# lightsaber.net
KiCad netlist of a schematic drawn in EAGLE
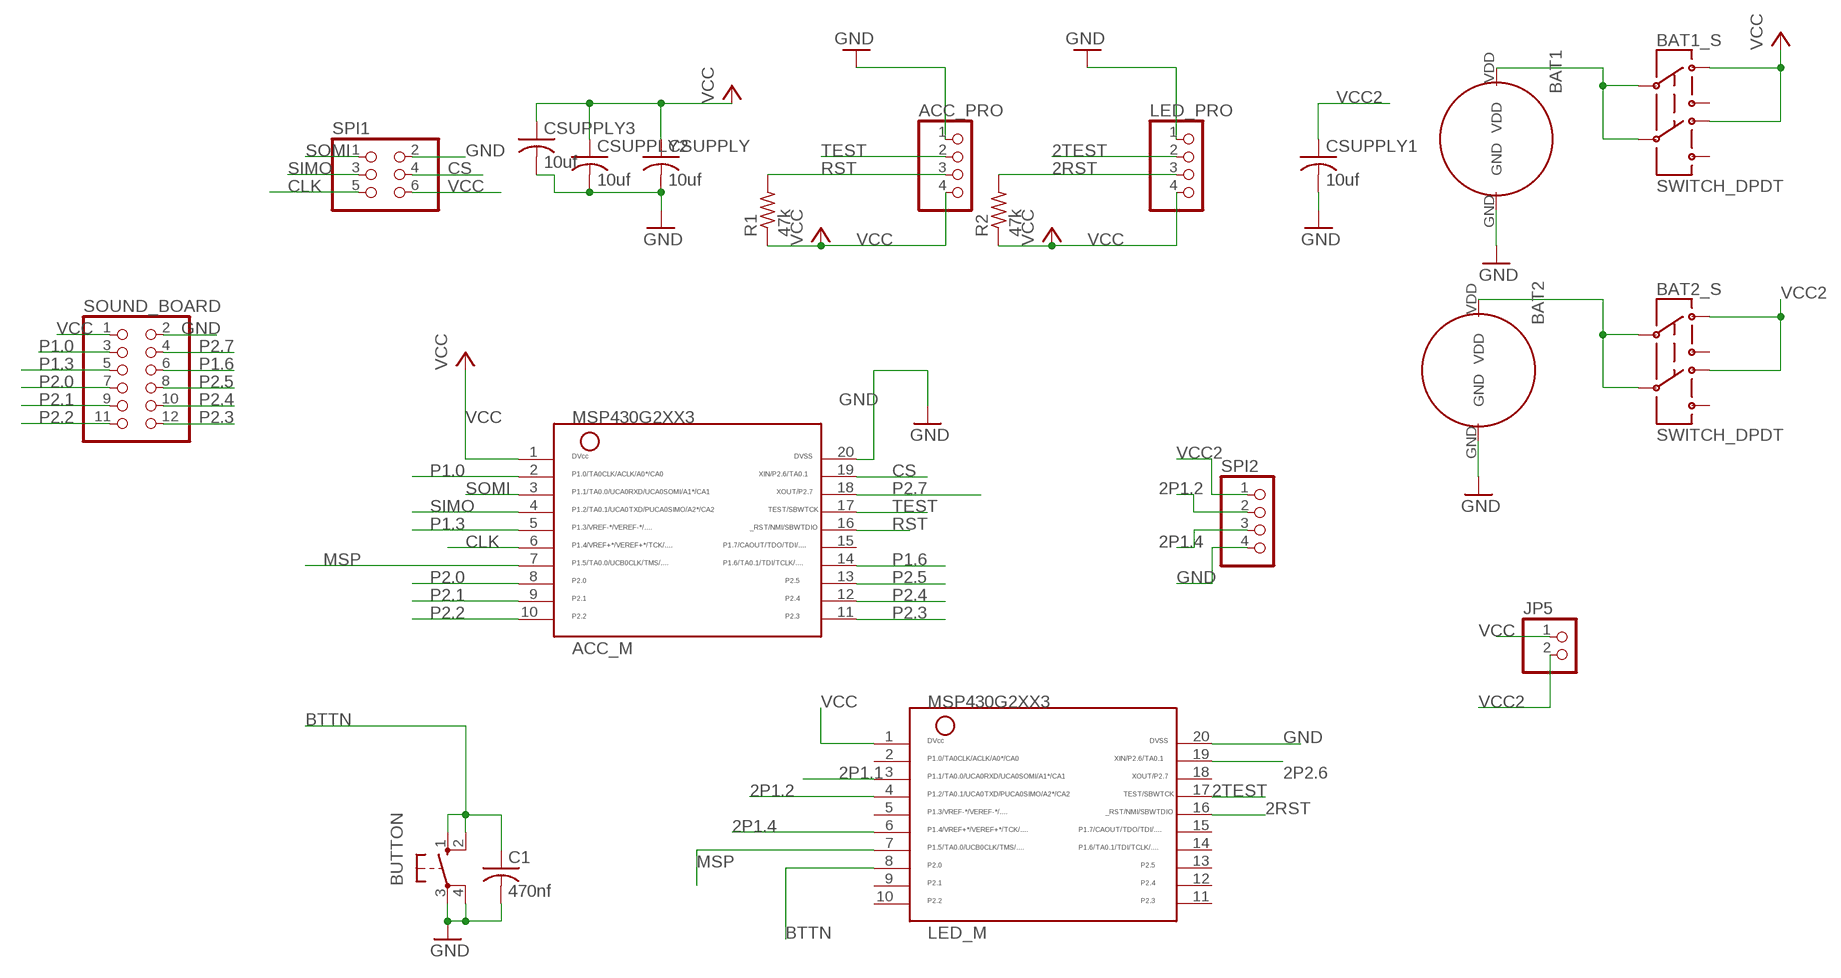
[diagram p0: schematic, sheet 1]

(export (version "E")
  (design (tool "Eeschema 10.0.6"))
  (components
    (comp (ref "ACC_M")
      (value "MSP430G2XX3TSSOP")
      (footprint "eagle-import:PW20")
      (libsource (lib "eagle-import") (part "MSP430G2XX3TSSOP"))
    )
    (comp (ref "ACC_PRO")
      (value "PINHD-1X4")
      (footprint "eagle-import:1X04")
      (libsource (lib "eagle-import") (part "PINHD-1X4"))
    )
    (comp (ref "BAT1")
      (value "BAT_PAD")
      (footprint "eagle-import:BATTERY_PAD1")
      (libsource (lib "eagle-import") (part "BAT_PAD"))
    )
    (comp (ref "BAT1_S")
      (value "SWITCH_DPDT")
      (footprint "eagle-import:JS_DPDT_TH")
      (libsource (lib "eagle-import") (part "SWITCH_DPDT"))
    )
    (comp (ref "BAT2")
      (value "BAT_PAD")
      (footprint "eagle-import:BATTERY_PAD1")
      (libsource (lib "eagle-import") (part "BAT_PAD"))
    )
    (comp (ref "BAT2_S")
      (value "SWITCH_DPDT")
      (footprint "eagle-import:JS_DPDT_TH")
      (libsource (lib "eagle-import") (part "SWITCH_DPDT"))
    )
    (comp (ref "BUTTON")
      (value "10-XX")
      (footprint "eagle-import:B3F-10XX")
      (fields (field (name "MPN") "B3F-1000"))
      (libsource (lib "eagle-import") (part "10-XX"))
    )
    (comp (ref "C1")
      (value "470nf")
      (footprint "eagle-import:C1206")
      (libsource (lib "eagle-import") (part "C-USC1206"))
    )
    (comp (ref "CSUPPLY")
      (value "10uf")
      (footprint "eagle-import:C1206")
      (libsource (lib "eagle-import") (part "C-USC1206"))
    )
    (comp (ref "CSUPPLY1")
      (value "10uf")
      (footprint "eagle-import:C1206")
      (libsource (lib "eagle-import") (part "C-USC1206"))
    )
    (comp (ref "CSUPPLY2")
      (value "10uf")
      (footprint "eagle-import:C1206")
      (libsource (lib "eagle-import") (part "C-USC1206"))
    )
    (comp (ref "CSUPPLY3")
      (value "10uf")
      (footprint "eagle-import:C1206")
      (libsource (lib "eagle-import") (part "C-USC1206"))
    )
    (comp (ref "JP5")
      (value "PINHD-1X2")
      (footprint "eagle-import:1X02")
      (libsource (lib "eagle-import") (part "PINHD-1X2"))
    )
    (comp (ref "LED_M")
      (value "MSP430G2XX3TSSOP")
      (footprint "eagle-import:PW20")
      (libsource (lib "eagle-import") (part "MSP430G2XX3TSSOP"))
    )
    (comp (ref "LED_PRO")
      (value "PINHD-1X4")
      (footprint "eagle-import:1X04")
      (libsource (lib "eagle-import") (part "PINHD-1X4"))
    )
    (comp (ref "R1")
      (value "47k")
      (footprint "eagle-import:R1206")
      (libsource (lib "eagle-import") (part "R-US_R1206"))
    )
    (comp (ref "R2")
      (value "47k")
      (footprint "eagle-import:R1206")
      (libsource (lib "eagle-import") (part "R-US_R1206"))
    )
    (comp (ref "SOUND_BOARD")
      (value "PINHD-2X6")
      (footprint "eagle-import:2X06")
      (libsource (lib "eagle-import") (part "PINHD-2X6"))
    )
    (comp (ref "SPI1")
      (value "PINHD-2X3")
      (footprint "eagle-import:2X03")
      (libsource (lib "eagle-import") (part "PINHD-2X3"))
    )
    (comp (ref "SPI2")
      (value "PINHD-1X4")
      (footprint "eagle-import:1X04")
      (libsource (lib "eagle-import") (part "PINHD-1X4"))
    )
  )
  (nets
    (net (code "1") (name "/2P1.1") (class "Default")
      (node (ref "LED_M") (pin "3") (pinfunction "3_3") (pintype "bidirectional"))
    )
    (net (code "2") (name "/2P1.2") (class "Default")
      (node (ref "LED_M") (pin "4") (pinfunction "4_4") (pintype "bidirectional"))
      (node (ref "SPI2") (pin "2") (pinfunction "2_2") (pintype "passive"))
    )
    (net (code "3") (name "/2P1.4") (class "Default")
      (node (ref "LED_M") (pin "6") (pinfunction "6_6") (pintype "bidirectional"))
      (node (ref "SPI2") (pin "3") (pinfunction "3_3") (pintype "passive"))
    )
    (net (code "4") (name "/2P2.6") (class "Default")
      (node (ref "LED_M") (pin "19") (pinfunction "19_19") (pintype "bidirectional"))
    )
    (net (code "5") (name "/2RST") (class "Default")
      (node (ref "LED_M") (pin "16") (pinfunction "16_16") (pintype "bidirectional"))
      (node (ref "LED_PRO") (pin "3") (pinfunction "3_3") (pintype "passive"))
      (node (ref "R2") (pin "2") (pinfunction "2_2") (pintype "passive"))
    )
    (net (code "6") (name "/2TEST") (class "Default")
      (node (ref "LED_M") (pin "17") (pinfunction "17_17") (pintype "bidirectional"))
      (node (ref "LED_PRO") (pin "2") (pinfunction "2_2") (pintype "passive"))
    )
    (net (code "7") (name "/BTTN") (class "Default")
      (node (ref "BUTTON") (pin "1") (pinfunction "S_1") (pintype "passive"))
      (node (ref "BUTTON") (pin "2") (pinfunction "S1_2") (pintype "passive"))
      (node (ref "C1") (pin "1") (pinfunction "1_1") (pintype "passive"))
      (node (ref "LED_M") (pin "8") (pinfunction "8_8") (pintype "bidirectional"))
    )
    (net (code "8") (name "/CLK") (class "Default")
      (node (ref "ACC_M") (pin "6") (pinfunction "6_6") (pintype "bidirectional"))
      (node (ref "SPI1") (pin "5") (pinfunction "5_5") (pintype "passive"))
    )
    (net (code "9") (name "/CS") (class "Default")
      (node (ref "ACC_M") (pin "19") (pinfunction "19_19") (pintype "bidirectional"))
      (node (ref "SPI1") (pin "4") (pinfunction "4_4") (pintype "passive"))
    )
    (net (code "10") (name "/MSP") (class "Default")
      (node (ref "ACC_M") (pin "7") (pinfunction "7_7") (pintype "bidirectional"))
      (node (ref "LED_M") (pin "7") (pinfunction "7_7") (pintype "bidirectional"))
    )
    (net (code "11") (name "/P1.0") (class "Default")
      (node (ref "ACC_M") (pin "2") (pinfunction "2_2") (pintype "bidirectional"))
      (node (ref "SOUND_BOARD") (pin "3") (pinfunction "3_3") (pintype "passive"))
    )
    (net (code "12") (name "/P1.3") (class "Default")
      (node (ref "ACC_M") (pin "5") (pinfunction "5_5") (pintype "bidirectional"))
      (node (ref "SOUND_BOARD") (pin "5") (pinfunction "5_5") (pintype "passive"))
    )
    (net (code "13") (name "/P1.6") (class "Default")
      (node (ref "ACC_M") (pin "14") (pinfunction "14_14") (pintype "bidirectional"))
      (node (ref "SOUND_BOARD") (pin "6") (pinfunction "6_6") (pintype "passive"))
    )
    (net (code "14") (name "/P2.0") (class "Default")
      (node (ref "ACC_M") (pin "8") (pinfunction "8_8") (pintype "bidirectional"))
      (node (ref "SOUND_BOARD") (pin "7") (pinfunction "7_7") (pintype "passive"))
    )
    (net (code "15") (name "/P2.1") (class "Default")
      (node (ref "ACC_M") (pin "9") (pinfunction "9_9") (pintype "bidirectional"))
      (node (ref "SOUND_BOARD") (pin "9") (pinfunction "9_9") (pintype "passive"))
    )
    (net (code "16") (name "/P2.2") (class "Default")
      (node (ref "ACC_M") (pin "10") (pinfunction "10_10") (pintype "bidirectional"))
      (node (ref "SOUND_BOARD") (pin "11") (pinfunction "11_11") (pintype "passive"))
    )
    (net (code "17") (name "/P2.3") (class "Default")
      (node (ref "ACC_M") (pin "11") (pinfunction "11_11") (pintype "bidirectional"))
      (node (ref "SOUND_BOARD") (pin "12") (pinfunction "12_12") (pintype "passive"))
    )
    (net (code "18") (name "/P2.4") (class "Default")
      (node (ref "ACC_M") (pin "12") (pinfunction "12_12") (pintype "bidirectional"))
      (node (ref "SOUND_BOARD") (pin "10") (pinfunction "10_10") (pintype "passive"))
    )
    (net (code "19") (name "/P2.5") (class "Default")
      (node (ref "ACC_M") (pin "13") (pinfunction "13_13") (pintype "bidirectional"))
      (node (ref "SOUND_BOARD") (pin "8") (pinfunction "8_8") (pintype "passive"))
    )
    (net (code "20") (name "/P2.7") (class "Default")
      (node (ref "ACC_M") (pin "18") (pinfunction "18_18") (pintype "bidirectional"))
      (node (ref "SOUND_BOARD") (pin "4") (pinfunction "4_4") (pintype "passive"))
    )
    (net (code "21") (name "/RST") (class "Default")
      (node (ref "ACC_M") (pin "16") (pinfunction "16_16") (pintype "bidirectional"))
      (node (ref "ACC_PRO") (pin "3") (pinfunction "3_3") (pintype "passive"))
      (node (ref "R1") (pin "2") (pinfunction "2_2") (pintype "passive"))
    )
    (net (code "22") (name "/SIMO") (class "Default")
      (node (ref "ACC_M") (pin "4") (pinfunction "4_4") (pintype "bidirectional"))
      (node (ref "SPI1") (pin "3") (pinfunction "3_3") (pintype "passive"))
    )
    (net (code "23") (name "/SOMI") (class "Default")
      (node (ref "ACC_M") (pin "3") (pinfunction "3_3") (pintype "bidirectional"))
      (node (ref "SPI1") (pin "1") (pinfunction "1_1") (pintype "passive"))
    )
    (net (code "24") (name "/TEST") (class "Default")
      (node (ref "ACC_M") (pin "17") (pinfunction "17_17") (pintype "bidirectional"))
      (node (ref "ACC_PRO") (pin "2") (pinfunction "2_2") (pintype "passive"))
    )
    (net (code "25") (name "/VCC2") (class "Default")
      (node (ref "BAT2_S") (pin "1") (pinfunction "1_1") (pintype "bidirectional"))
      (node (ref "BAT2_S") (pin "4") (pinfunction "4_4") (pintype "bidirectional"))
      (node (ref "CSUPPLY1") (pin "1") (pinfunction "1_1") (pintype "passive"))
      (node (ref "JP5") (pin "2") (pinfunction "2_2") (pintype "passive"))
      (node (ref "SPI2") (pin "1") (pinfunction "1_1") (pintype "passive"))
    )
    (net (code "26") (name "GND") (class "Default")
      (node (ref "ACC_M") (pin "20") (pinfunction "20_20") (pintype "bidirectional"))
      (node (ref "ACC_PRO") (pin "1") (pinfunction "1_1") (pintype "passive"))
      (node (ref "BAT1") (pin "GND") (pinfunction "GND_GND") (pintype "bidirectional"))
      (node (ref "BAT2") (pin "GND") (pinfunction "GND_GND") (pintype "bidirectional"))
      (node (ref "BUTTON") (pin "3") (pinfunction "P_3") (pintype "passive"))
      (node (ref "BUTTON") (pin "4") (pinfunction "P1_4") (pintype "passive"))
      (node (ref "C1") (pin "2") (pinfunction "2_2") (pintype "passive"))
      (node (ref "CSUPPLY") (pin "2") (pinfunction "2_2") (pintype "passive"))
      (node (ref "CSUPPLY1") (pin "2") (pinfunction "2_2") (pintype "passive"))
      (node (ref "CSUPPLY2") (pin "2") (pinfunction "2_2") (pintype "passive"))
      (node (ref "CSUPPLY3") (pin "2") (pinfunction "2_2") (pintype "passive"))
      (node (ref "LED_M") (pin "20") (pinfunction "20_20") (pintype "bidirectional"))
      (node (ref "LED_PRO") (pin "1") (pinfunction "1_1") (pintype "passive"))
      (node (ref "SOUND_BOARD") (pin "2") (pinfunction "2_2") (pintype "passive"))
      (node (ref "SPI1") (pin "2") (pinfunction "2_2") (pintype "passive"))
      (node (ref "SPI2") (pin "4") (pinfunction "4_4") (pintype "passive"))
    )
    (net (code "27") (name "Net-(BAT1-PadVDD)") (class "Default")
      (node (ref "BAT1") (pin "VDD") (pinfunction "VDD_VDD") (pintype "bidirectional"))
      (node (ref "BAT1_S") (pin "2") (pinfunction "2_2") (pintype "bidirectional"))
      (node (ref "BAT1_S") (pin "5") (pinfunction "5_5") (pintype "bidirectional"))
    )
    (net (code "28") (name "Net-(BAT2-PadVDD)") (class "Default")
      (node (ref "BAT2") (pin "VDD") (pinfunction "VDD_VDD") (pintype "bidirectional"))
      (node (ref "BAT2_S") (pin "2") (pinfunction "2_2") (pintype "bidirectional"))
      (node (ref "BAT2_S") (pin "5") (pinfunction "5_5") (pintype "bidirectional"))
    )
    (net (code "29") (name "VCC") (class "Default")
      (node (ref "ACC_M") (pin "1") (pinfunction "1_1") (pintype "bidirectional"))
      (node (ref "ACC_PRO") (pin "4") (pinfunction "4_4") (pintype "passive"))
      (node (ref "BAT1_S") (pin "1") (pinfunction "1_1") (pintype "bidirectional"))
      (node (ref "BAT1_S") (pin "4") (pinfunction "4_4") (pintype "bidirectional"))
      (node (ref "CSUPPLY") (pin "1") (pinfunction "1_1") (pintype "passive"))
      (node (ref "CSUPPLY2") (pin "1") (pinfunction "1_1") (pintype "passive"))
      (node (ref "CSUPPLY3") (pin "1") (pinfunction "1_1") (pintype "passive"))
      (node (ref "JP5") (pin "1") (pinfunction "1_1") (pintype "passive"))
      (node (ref "LED_M") (pin "1") (pinfunction "1_1") (pintype "bidirectional"))
      (node (ref "LED_PRO") (pin "4") (pinfunction "4_4") (pintype "passive"))
      (node (ref "R1") (pin "1") (pinfunction "1_1") (pintype "passive"))
      (node (ref "R2") (pin "1") (pinfunction "1_1") (pintype "passive"))
      (node (ref "SOUND_BOARD") (pin "1") (pinfunction "1_1") (pintype "passive"))
      (node (ref "SPI1") (pin "6") (pinfunction "6_6") (pintype "passive"))
    )
    (net (code "30") (name "unconnected-(ACC_M-Pad15)") (class "Default")
      (node (ref "ACC_M") (pin "15") (pinfunction "15_15") (pintype "bidirectional"))
    )
    (net (code "31") (name "unconnected-(BAT1_S-Pad3)") (class "Default")
      (node (ref "BAT1_S") (pin "3") (pinfunction "3_3") (pintype "bidirectional"))
    )
    (net (code "32") (name "unconnected-(BAT1_S-Pad6)") (class "Default")
      (node (ref "BAT1_S") (pin "6") (pinfunction "6_6") (pintype "bidirectional"))
    )
    (net (code "33") (name "unconnected-(BAT2_S-Pad3)") (class "Default")
      (node (ref "BAT2_S") (pin "3") (pinfunction "3_3") (pintype "bidirectional"))
    )
    (net (code "34") (name "unconnected-(BAT2_S-Pad6)") (class "Default")
      (node (ref "BAT2_S") (pin "6") (pinfunction "6_6") (pintype "bidirectional"))
    )
    (net (code "35") (name "unconnected-(LED_M-Pad2)") (class "Default")
      (node (ref "LED_M") (pin "2") (pinfunction "2_2") (pintype "bidirectional"))
    )
    (net (code "36") (name "unconnected-(LED_M-Pad5)") (class "Default")
      (node (ref "LED_M") (pin "5") (pinfunction "5_5") (pintype "bidirectional"))
    )
    (net (code "37") (name "unconnected-(LED_M-Pad9)") (class "Default")
      (node (ref "LED_M") (pin "9") (pinfunction "9_9") (pintype "bidirectional"))
    )
    (net (code "38") (name "unconnected-(LED_M-Pad10)") (class "Default")
      (node (ref "LED_M") (pin "10") (pinfunction "10_10") (pintype "bidirectional"))
    )
    (net (code "39") (name "unconnected-(LED_M-Pad11)") (class "Default")
      (node (ref "LED_M") (pin "11") (pinfunction "11_11") (pintype "bidirectional"))
    )
    (net (code "40") (name "unconnected-(LED_M-Pad12)") (class "Default")
      (node (ref "LED_M") (pin "12") (pinfunction "12_12") (pintype "bidirectional"))
    )
    (net (code "41") (name "unconnected-(LED_M-Pad13)") (class "Default")
      (node (ref "LED_M") (pin "13") (pinfunction "13_13") (pintype "bidirectional"))
    )
    (net (code "42") (name "unconnected-(LED_M-Pad14)") (class "Default")
      (node (ref "LED_M") (pin "14") (pinfunction "14_14") (pintype "bidirectional"))
    )
    (net (code "43") (name "unconnected-(LED_M-Pad15)") (class "Default")
      (node (ref "LED_M") (pin "15") (pinfunction "15_15") (pintype "bidirectional"))
    )
    (net (code "44") (name "unconnected-(LED_M-Pad18)") (class "Default")
      (node (ref "LED_M") (pin "18") (pinfunction "18_18") (pintype "bidirectional"))
    )
  )
)
